# test.net
KiCad netlist of a schematic drawn in Altium Designer
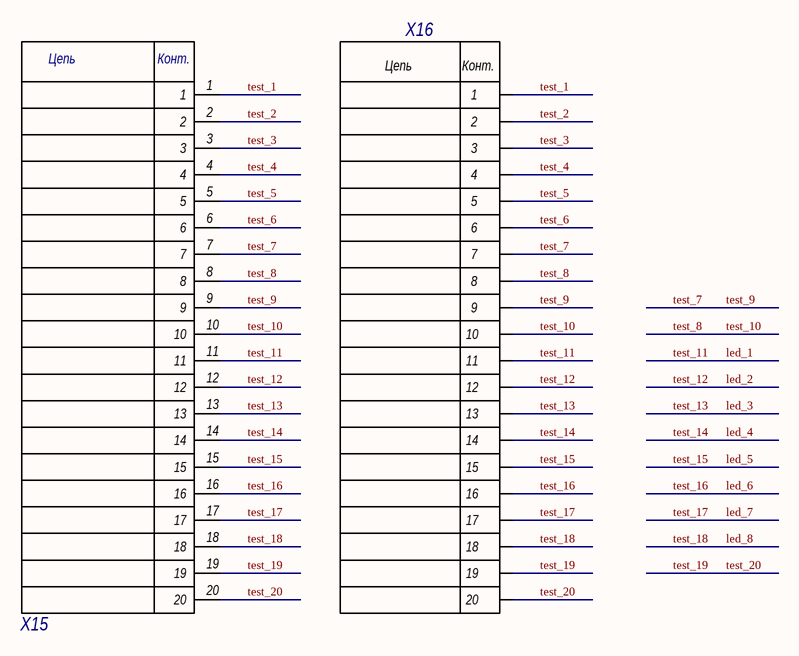
[diagram p0: test.SchDoc]

(export (version "E")
  (design (tool "Eeschema 10.0.6"))
  (components
    (comp (ref "X15")
      (value "87831-2020")
      (footprint "87831-2020")
      (description "CONN HEADER VERT 20POS 2MM")
      (fields (field (name "MANUFACTURER") "Molex"))
      (libsource (lib "DatabaseSVN") (part "CON_20"))
    )
    (comp (ref "X16")
      (value "PLD-20")
      (footprint "PLD-20")
      (description "штыри на плату двурядные")
      (fields (field (name "PARTNUMBER") "PLD-20 2.54mm"))
      (libsource (lib "DatabaseSVN") (part "20_pins"))
    )
  )
  (nets
    (net (code "1") (name "/led_1") (class "Default")
      (node (ref "X15") (pin "11") (pinfunction "11_11") (pintype "passive"))
      (node (ref "X16") (pin "11") (pinfunction "11_11") (pintype "passive"))
    )
    (net (code "2") (name "/led_2") (class "Default")
      (node (ref "X15") (pin "12") (pinfunction "12_12") (pintype "passive"))
      (node (ref "X16") (pin "12") (pinfunction "12_12") (pintype "passive"))
    )
    (net (code "3") (name "/led_3") (class "Default")
      (node (ref "X15") (pin "13") (pinfunction "13_13") (pintype "passive"))
      (node (ref "X16") (pin "13") (pinfunction "13_13") (pintype "passive"))
    )
    (net (code "4") (name "/led_4") (class "Default")
      (node (ref "X15") (pin "14") (pinfunction "14_14") (pintype "passive"))
      (node (ref "X16") (pin "14") (pinfunction "14_14") (pintype "passive"))
    )
    (net (code "5") (name "/led_5") (class "Default")
      (node (ref "X15") (pin "15") (pinfunction "15_15") (pintype "passive"))
      (node (ref "X16") (pin "15") (pinfunction "15_15") (pintype "passive"))
    )
    (net (code "6") (name "/led_6") (class "Default")
      (node (ref "X15") (pin "16") (pinfunction "16_16") (pintype "passive"))
      (node (ref "X16") (pin "16") (pinfunction "16_16") (pintype "passive"))
    )
    (net (code "7") (name "/led_7") (class "Default")
      (node (ref "X15") (pin "17") (pinfunction "17_17") (pintype "passive"))
      (node (ref "X16") (pin "17") (pinfunction "17_17") (pintype "passive"))
    )
    (net (code "8") (name "/led_8") (class "Default")
      (node (ref "X15") (pin "18") (pinfunction "18_18") (pintype "passive"))
      (node (ref "X16") (pin "18") (pinfunction "18_18") (pintype "passive"))
    )
    (net (code "9") (name "/test_1") (class "Default")
      (node (ref "X15") (pin "1") (pinfunction "1_1") (pintype "passive"))
      (node (ref "X16") (pin "1") (pinfunction "1_1") (pintype "passive"))
    )
    (net (code "10") (name "/test_2") (class "Default")
      (node (ref "X15") (pin "2") (pinfunction "2_2") (pintype "passive"))
      (node (ref "X16") (pin "2") (pinfunction "2_2") (pintype "passive"))
    )
    (net (code "11") (name "/test_3") (class "Default")
      (node (ref "X15") (pin "3") (pinfunction "3_3") (pintype "passive"))
      (node (ref "X16") (pin "3") (pinfunction "3_3") (pintype "passive"))
    )
    (net (code "12") (name "/test_4") (class "Default")
      (node (ref "X15") (pin "4") (pinfunction "4_4") (pintype "passive"))
      (node (ref "X16") (pin "4") (pinfunction "4_4") (pintype "passive"))
    )
    (net (code "13") (name "/test_5") (class "Default")
      (node (ref "X15") (pin "5") (pinfunction "5_5") (pintype "passive"))
      (node (ref "X16") (pin "5") (pinfunction "5_5") (pintype "passive"))
    )
    (net (code "14") (name "/test_6") (class "Default")
      (node (ref "X15") (pin "6") (pinfunction "6_6") (pintype "passive"))
      (node (ref "X16") (pin "6") (pinfunction "6_6") (pintype "passive"))
    )
    (net (code "15") (name "/test_7") (class "Default")
      (node (ref "X15") (pin "7") (pinfunction "7_7") (pintype "passive"))
      (node (ref "X15") (pin "9") (pinfunction "9_9") (pintype "passive"))
      (node (ref "X16") (pin "7") (pinfunction "7_7") (pintype "passive"))
      (node (ref "X16") (pin "9") (pinfunction "9_9") (pintype "passive"))
    )
    (net (code "16") (name "/test_10") (class "Default")
      (node (ref "X15") (pin "10") (pinfunction "10_10") (pintype "passive"))
      (node (ref "X15") (pin "8") (pinfunction "8_8") (pintype "passive"))
      (node (ref "X16") (pin "10") (pinfunction "10_10") (pintype "passive"))
      (node (ref "X16") (pin "8") (pinfunction "8_8") (pintype "passive"))
    )
    (net (code "17") (name "/test_19") (class "Default")
      (node (ref "X15") (pin "19") (pinfunction "19_19") (pintype "passive"))
      (node (ref "X15") (pin "20") (pinfunction "20_20") (pintype "passive"))
      (node (ref "X16") (pin "19") (pinfunction "19_19") (pintype "passive"))
      (node (ref "X16") (pin "20") (pinfunction "20_20") (pintype "passive"))
    )
  )
)
